# STM32F103RCT6_2_0.net
KiCad netlist of a schematic drawn in EasyEDA Pro
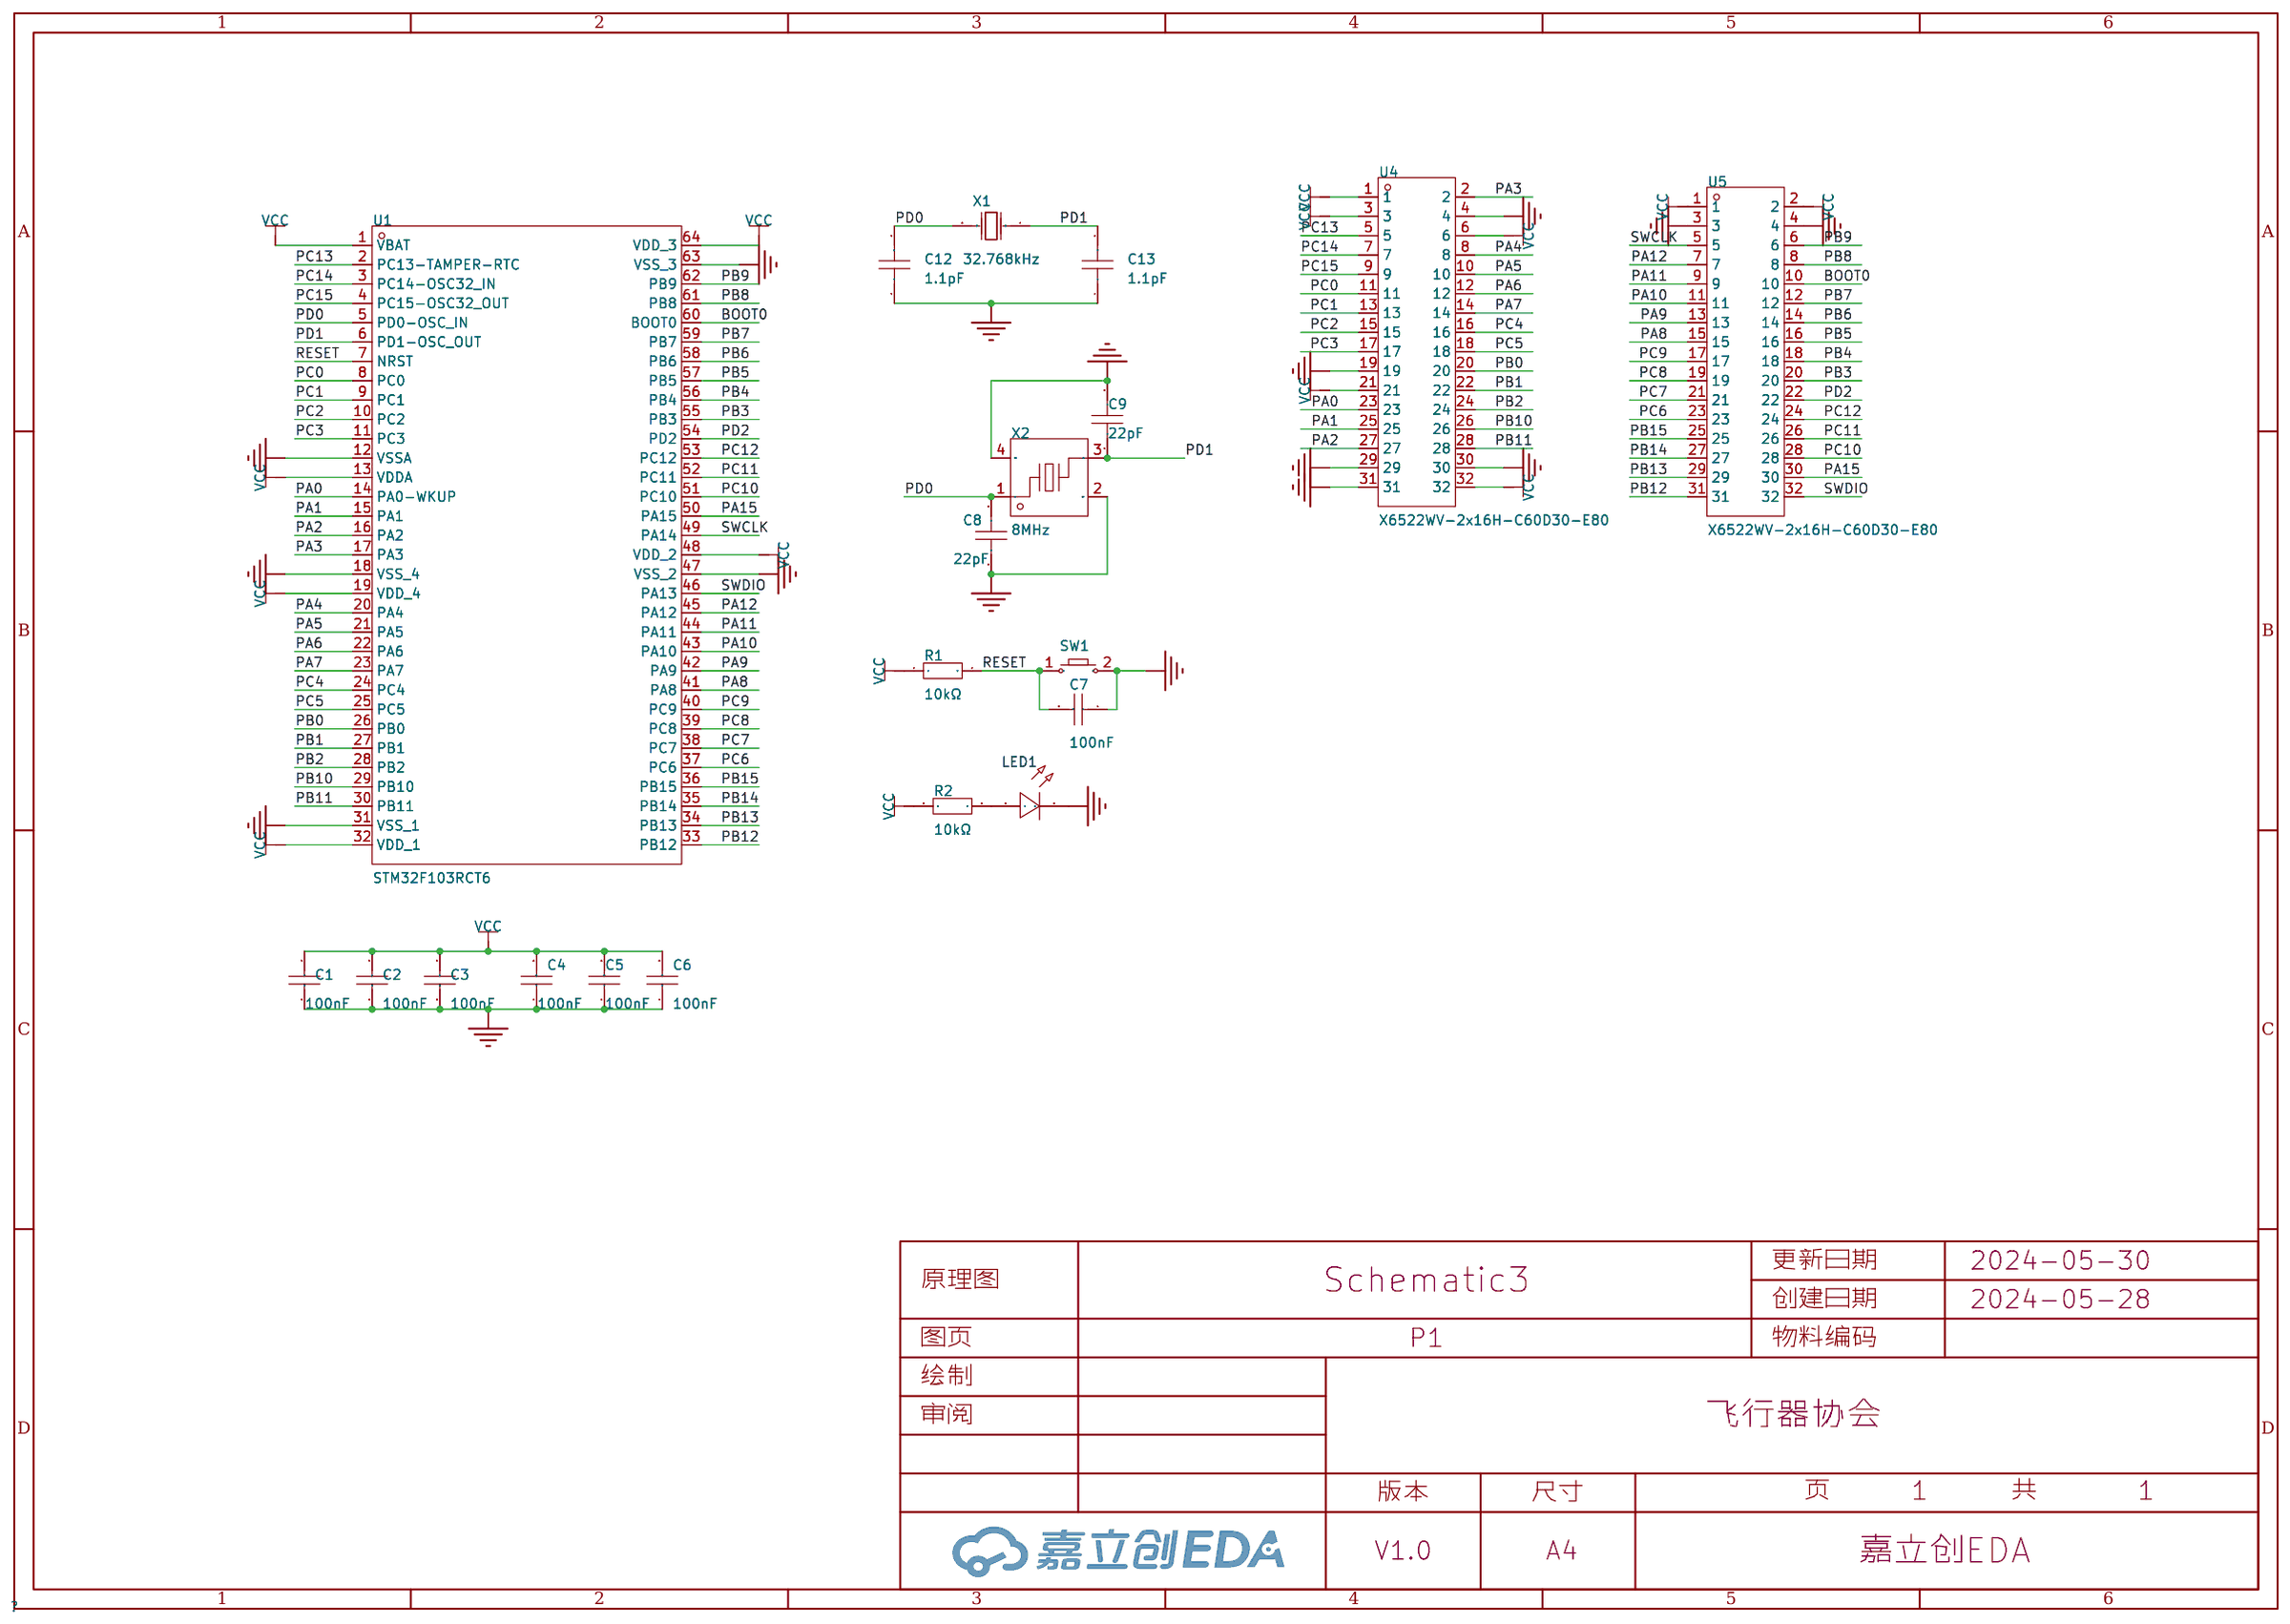
[diagram p0: schematic sheet]

(export (version "E")
  (design (tool "Eeschema 10.0.6"))
  (components
    (comp (ref "C1")
      (value "100nF")
      (footprint "easyedapro:C0805")
      (description "容值:100nF;精度:±10%;额定电压:50V;材质(温度系数):X7R;")
      (fields
        (field (name "Manufacturer Part") "CC0805KRX7R9BB104")
        (field (name "Manufacturer") "YAGEO(国巨)")
      )
      (libsource (lib "easyedapro") (part "CC0805KRX7R9BB104"))
    )
    (comp (ref "C2")
      (value "100nF")
      (footprint "easyedapro:C0805")
      (description "容值:100nF;精度:±10%;额定电压:50V;材质(温度系数):X7R;")
      (fields
        (field (name "Manufacturer Part") "CC0805KRX7R9BB104")
        (field (name "Manufacturer") "YAGEO(国巨)")
      )
      (libsource (lib "easyedapro") (part "CC0805KRX7R9BB104"))
    )
    (comp (ref "C3")
      (value "100nF")
      (footprint "easyedapro:C0805")
      (description "容值:100nF;精度:±10%;额定电压:50V;材质(温度系数):X7R;")
      (fields
        (field (name "Manufacturer Part") "CC0805KRX7R9BB104")
        (field (name "Manufacturer") "YAGEO(国巨)")
      )
      (libsource (lib "easyedapro") (part "CC0805KRX7R9BB104"))
    )
    (comp (ref "C4")
      (value "100nF")
      (footprint "easyedapro:C0805")
      (description "容值:100nF;精度:±10%;额定电压:50V;材质(温度系数):X7R;")
      (fields
        (field (name "Manufacturer Part") "CC0805KRX7R9BB104")
        (field (name "Manufacturer") "YAGEO(国巨)")
      )
      (libsource (lib "easyedapro") (part "CC0805KRX7R9BB104"))
    )
    (comp (ref "C5")
      (value "100nF")
      (footprint "easyedapro:C0805")
      (description "容值:100nF;精度:±10%;额定电压:50V;材质(温度系数):X7R;")
      (fields
        (field (name "Manufacturer Part") "CC0805KRX7R9BB104")
        (field (name "Manufacturer") "YAGEO(国巨)")
      )
      (libsource (lib "easyedapro") (part "CC0805KRX7R9BB104"))
    )
    (comp (ref "C6")
      (value "100nF")
      (footprint "easyedapro:C0805")
      (description "容值:100nF;精度:±10%;额定电压:50V;材质(温度系数):X7R;")
      (fields
        (field (name "Manufacturer Part") "CC0805KRX7R9BB104")
        (field (name "Manufacturer") "YAGEO(国巨)")
      )
      (libsource (lib "easyedapro") (part "CC0805KRX7R9BB104"))
    )
    (comp (ref "C7")
      (value "100nF")
      (footprint "easyedapro:C0805")
      (description "容值:100nF;精度:±10%;额定电压:50V;材质(温度系数):X7R;")
      (fields
        (field (name "Manufacturer Part") "CC0805KRX7R9BB104")
        (field (name "Manufacturer") "YAGEO(国巨)")
      )
      (libsource (lib "easyedapro") (part "CC0805KRX7R9BB104"))
    )
    (comp (ref "C8")
      (value "22pF")
      (footprint "easyedapro:C0805")
      (description "容值:22pF;精度:±5%;额定电压:50V;材质(温度系数):C0G;")
      (fields (field (name "Manufacturer Part") "0805CG220J500NT") (field (name "Manufacturer") "FH(风华)"))
      (libsource (lib "easyedapro") (part "0805CG220J500NT_C24658"))
    )
    (comp (ref "C9")
      (value "22pF")
      (footprint "easyedapro:C0805")
      (description "容值:22pF;精度:±5%;额定电压:50V;材质(温度系数):C0G;")
      (fields (field (name "Manufacturer Part") "0805CG220J500NT") (field (name "Manufacturer") "FH(风华)"))
      (libsource (lib "easyedapro") (part "0805CG220J500NT_C24658"))
    )
    (comp (ref "C12")
      (value "1.1pF")
      (footprint "easyedapro:C0805")
      (description "容值:1.1pF;额定电压:250V;材质(温度系数):C0G;")
      (fields (field (name "Manufacturer Part") "VJ0805D1R1CXPAC") (field (name "Manufacturer") "VISHAY(威世)"))
      (libsource (lib "easyedapro") (part "VJ0805D1R1CXPAC"))
    )
    (comp (ref "C13")
      (value "1.1pF")
      (footprint "easyedapro:C0805")
      (description "容值:1.1pF;额定电压:250V;材质(温度系数):C0G;")
      (fields (field (name "Manufacturer Part") "VJ0805D1R1CXPAC") (field (name "Manufacturer") "VISHAY(威世)"))
      (libsource (lib "easyedapro") (part "VJ0805D1R1CXPAC"))
    )
    (comp (ref "LED1")
      (value "~")
      (footprint "easyedapro:LED_0805")
      (libsource (lib "easyedapro") (part "LED_G"))
    )
    (comp (ref "R1")
      (value "10kΩ")
      (footprint "easyedapro:R0805")
      (description "电阻类型:厚膜电阻;阻值:10kΩ;精度:±1%;功率:125mW;最大工作电压:150V;温度系数:±100ppm/°C;")
      (fields
        (field (name "Manufacturer Part") "0805W8F1002T5E")
        (field (name "Manufacturer") "UNI-ROYAL(厚声)")
      )
      (libsource (lib "easyedapro") (part "0805W8F1002T5E"))
    )
    (comp (ref "R2")
      (value "10kΩ")
      (footprint "easyedapro:R0805")
      (description "电阻类型:厚膜电阻;阻值:10kΩ;精度:±1%;功率:125mW;最大工作电压:150V;温度系数:±100ppm/°C;")
      (fields
        (field (name "Manufacturer Part") "0805W8F1002T5E")
        (field (name "Manufacturer") "UNI-ROYAL(厚声)")
      )
      (libsource (lib "easyedapro") (part "0805W8F1002T5E"))
    )
    (comp (ref "SW1")
      (value "~")
      (footprint "easyedapro:Key_SMD_3.6x6.1x2.5")
      (libsource (lib "easyedapro") (part "轻触按键x2"))
    )
    (comp (ref "U1")
      (value "STM32F103RCT6")
      (footprint "easyedapro:LQFP-64_L10.0-W10.0-P0.50-LS12.0-BL")
      (fields (field (name "Manufacturer") "ST(意法半导体)"))
      (libsource (lib "easyedapro") (part "STM32F103RCT6"))
    )
    (comp (ref "U4")
      (value "X6522WV-2x16H-C60D30-E80")
      (footprint "easyedapro:HDR-TH_32P-P2.54-V-M-R2-C16-S2.54-3")
      (fields (field (name "Manufacturer") "XKB Connection(中国星坤)"))
      (libsource (lib "easyedapro") (part "X6522WV-2X16H-C60D30-E80"))
    )
    (comp (ref "U5")
      (value "X6522WV-2x16H-C60D30-E80")
      (footprint "easyedapro:HDR-TH_32P-P2.54-V-M-R2-C16-S2.54-3")
      (fields (field (name "Manufacturer") "XKB Connection(中国星坤)"))
      (libsource (lib "easyedapro") (part "X6522WV-2X16H-C60D30-E80"))
    )
    (comp (ref "X1")
      (value "32.768kHz")
      (footprint "easyedapro:OSC-TH_BD2.0-P0.70-D0.3")
      (description "晶振类型:-;频率:-;外接负载电容:-;")
      (fields (field (name "Manufacturer Part") "DT-26 32.768KHz") (field (name "Manufacturer") "KDS(大真空)"))
      (libsource (lib "easyedapro") (part "DT-26 32.768KHz"))
    )
    (comp (ref "X2")
      (value "8MHz")
      (footprint "easyedapro:CRYSTAL-SMD_4P-L3.2-W2.5-BL")
      (description "晶振类型:-;频率:8MHz;常温频差:±10ppm;外接负载电容:20pF;频率稳定度(全温):±30ppm;")
      (fields
        (field (name "Manufacturer Part") "3225 8M 20PF 10PPM")
        (field (name "Manufacturer") "SST(索斯特)")
      )
      (libsource (lib "easyedapro") (part "3225 8M 20PF 10PPM"))
    )
  )
  (nets
    (net (code "1") (name "/BOOT0") (class "Default")
      (node (ref "U1") (pin "60") (pinfunction "BOOT0_60") (pintype "unspecified"))
      (node (ref "U5") (pin "10") (pinfunction "10_10") (pintype "unspecified"))
    )
    (net (code "2") (name "/PA0") (class "Default")
      (node (ref "U1") (pin "14") (pinfunction "PA0-WKUP_14") (pintype "unspecified"))
      (node (ref "U4") (pin "23") (pinfunction "23_23") (pintype "unspecified"))
    )
    (net (code "3") (name "/PA1") (class "Default")
      (node (ref "U1") (pin "15") (pinfunction "PA1_15") (pintype "unspecified"))
      (node (ref "U4") (pin "25") (pinfunction "25_25") (pintype "unspecified"))
    )
    (net (code "4") (name "/PA2") (class "Default")
      (node (ref "U1") (pin "16") (pinfunction "PA2_16") (pintype "unspecified"))
      (node (ref "U4") (pin "27") (pinfunction "27_27") (pintype "unspecified"))
    )
    (net (code "5") (name "/PA3") (class "Default")
      (node (ref "U1") (pin "17") (pinfunction "PA3_17") (pintype "unspecified"))
      (node (ref "U4") (pin "2") (pinfunction "2_2") (pintype "unspecified"))
    )
    (net (code "6") (name "/PA4") (class "Default")
      (node (ref "U1") (pin "20") (pinfunction "PA4_20") (pintype "unspecified"))
      (node (ref "U4") (pin "8") (pinfunction "8_8") (pintype "unspecified"))
    )
    (net (code "7") (name "/PA5") (class "Default")
      (node (ref "U1") (pin "21") (pinfunction "PA5_21") (pintype "unspecified"))
      (node (ref "U4") (pin "10") (pinfunction "10_10") (pintype "unspecified"))
    )
    (net (code "8") (name "/PA6") (class "Default")
      (node (ref "U1") (pin "22") (pinfunction "PA6_22") (pintype "unspecified"))
      (node (ref "U4") (pin "12") (pinfunction "12_12") (pintype "unspecified"))
    )
    (net (code "9") (name "/PA7") (class "Default")
      (node (ref "U1") (pin "23") (pinfunction "PA7_23") (pintype "unspecified"))
      (node (ref "U4") (pin "14") (pinfunction "14_14") (pintype "unspecified"))
    )
    (net (code "10") (name "/PA8") (class "Default")
      (node (ref "U1") (pin "41") (pinfunction "PA8_41") (pintype "unspecified"))
      (node (ref "U5") (pin "15") (pinfunction "15_15") (pintype "unspecified"))
    )
    (net (code "11") (name "/PA9") (class "Default")
      (node (ref "U1") (pin "42") (pinfunction "PA9_42") (pintype "unspecified"))
      (node (ref "U5") (pin "13") (pinfunction "13_13") (pintype "unspecified"))
    )
    (net (code "12") (name "/PA10") (class "Default")
      (node (ref "U1") (pin "43") (pinfunction "PA10_43") (pintype "unspecified"))
      (node (ref "U5") (pin "11") (pinfunction "11_11") (pintype "unspecified"))
    )
    (net (code "13") (name "/PA11") (class "Default")
      (node (ref "U1") (pin "44") (pinfunction "PA11_44") (pintype "unspecified"))
      (node (ref "U5") (pin "9") (pinfunction "9_9") (pintype "unspecified"))
    )
    (net (code "14") (name "/PA12") (class "Default")
      (node (ref "U1") (pin "45") (pinfunction "PA12_45") (pintype "unspecified"))
      (node (ref "U5") (pin "7") (pinfunction "7_7") (pintype "unspecified"))
    )
    (net (code "15") (name "/PA15") (class "Default")
      (node (ref "U1") (pin "50") (pinfunction "PA15_50") (pintype "unspecified"))
      (node (ref "U5") (pin "30") (pinfunction "30_30") (pintype "unspecified"))
    )
    (net (code "16") (name "/PB0") (class "Default")
      (node (ref "U1") (pin "26") (pinfunction "PB0_26") (pintype "unspecified"))
      (node (ref "U4") (pin "20") (pinfunction "20_20") (pintype "unspecified"))
    )
    (net (code "17") (name "/PB1") (class "Default")
      (node (ref "U1") (pin "27") (pinfunction "PB1_27") (pintype "unspecified"))
      (node (ref "U4") (pin "22") (pinfunction "22_22") (pintype "unspecified"))
    )
    (net (code "18") (name "/PB2") (class "Default")
      (node (ref "U1") (pin "28") (pinfunction "PB2_28") (pintype "unspecified"))
      (node (ref "U4") (pin "24") (pinfunction "24_24") (pintype "unspecified"))
    )
    (net (code "19") (name "/PB3") (class "Default")
      (node (ref "U1") (pin "55") (pinfunction "PB3_55") (pintype "unspecified"))
      (node (ref "U5") (pin "20") (pinfunction "20_20") (pintype "unspecified"))
    )
    (net (code "20") (name "/PB4") (class "Default")
      (node (ref "U1") (pin "56") (pinfunction "PB4_56") (pintype "unspecified"))
      (node (ref "U5") (pin "18") (pinfunction "18_18") (pintype "unspecified"))
    )
    (net (code "21") (name "/PB5") (class "Default")
      (node (ref "U1") (pin "57") (pinfunction "PB5_57") (pintype "unspecified"))
      (node (ref "U5") (pin "16") (pinfunction "16_16") (pintype "unspecified"))
    )
    (net (code "22") (name "/PB6") (class "Default")
      (node (ref "U1") (pin "58") (pinfunction "PB6_58") (pintype "unspecified"))
      (node (ref "U5") (pin "14") (pinfunction "14_14") (pintype "unspecified"))
    )
    (net (code "23") (name "/PB7") (class "Default")
      (node (ref "U1") (pin "59") (pinfunction "PB7_59") (pintype "unspecified"))
      (node (ref "U5") (pin "12") (pinfunction "12_12") (pintype "unspecified"))
    )
    (net (code "24") (name "/PB8") (class "Default")
      (node (ref "U1") (pin "61") (pinfunction "PB8_61") (pintype "unspecified"))
      (node (ref "U5") (pin "8") (pinfunction "8_8") (pintype "unspecified"))
    )
    (net (code "25") (name "/PB9") (class "Default")
      (node (ref "U1") (pin "62") (pinfunction "PB9_62") (pintype "unspecified"))
      (node (ref "U5") (pin "6") (pinfunction "6_6") (pintype "unspecified"))
    )
    (net (code "26") (name "/PB10") (class "Default")
      (node (ref "U1") (pin "29") (pinfunction "PB10_29") (pintype "unspecified"))
      (node (ref "U4") (pin "26") (pinfunction "26_26") (pintype "unspecified"))
    )
    (net (code "27") (name "/PB11") (class "Default")
      (node (ref "U1") (pin "30") (pinfunction "PB11_30") (pintype "unspecified"))
      (node (ref "U4") (pin "28") (pinfunction "28_28") (pintype "unspecified"))
    )
    (net (code "28") (name "/PB12") (class "Default")
      (node (ref "U1") (pin "33") (pinfunction "PB12_33") (pintype "unspecified"))
      (node (ref "U5") (pin "31") (pinfunction "31_31") (pintype "unspecified"))
    )
    (net (code "29") (name "/PB13") (class "Default")
      (node (ref "U1") (pin "34") (pinfunction "PB13_34") (pintype "unspecified"))
      (node (ref "U5") (pin "29") (pinfunction "29_29") (pintype "unspecified"))
    )
    (net (code "30") (name "/PB14") (class "Default")
      (node (ref "U1") (pin "35") (pinfunction "PB14_35") (pintype "unspecified"))
      (node (ref "U5") (pin "27") (pinfunction "27_27") (pintype "unspecified"))
    )
    (net (code "31") (name "/PB15") (class "Default")
      (node (ref "U1") (pin "36") (pinfunction "PB15_36") (pintype "unspecified"))
      (node (ref "U5") (pin "25") (pinfunction "25_25") (pintype "unspecified"))
    )
    (net (code "32") (name "/PC0") (class "Default")
      (node (ref "U1") (pin "8") (pinfunction "PC0_8") (pintype "unspecified"))
      (node (ref "U4") (pin "11") (pinfunction "11_11") (pintype "unspecified"))
    )
    (net (code "33") (name "/PC1") (class "Default")
      (node (ref "U1") (pin "9") (pinfunction "PC1_9") (pintype "unspecified"))
      (node (ref "U4") (pin "13") (pinfunction "13_13") (pintype "unspecified"))
    )
    (net (code "34") (name "/PC2") (class "Default")
      (node (ref "U1") (pin "10") (pinfunction "PC2_10") (pintype "unspecified"))
      (node (ref "U4") (pin "15") (pinfunction "15_15") (pintype "unspecified"))
    )
    (net (code "35") (name "/PC3") (class "Default")
      (node (ref "U1") (pin "11") (pinfunction "PC3_11") (pintype "unspecified"))
      (node (ref "U4") (pin "17") (pinfunction "17_17") (pintype "unspecified"))
    )
    (net (code "36") (name "/PC4") (class "Default")
      (node (ref "U1") (pin "24") (pinfunction "PC4_24") (pintype "unspecified"))
      (node (ref "U4") (pin "16") (pinfunction "16_16") (pintype "unspecified"))
    )
    (net (code "37") (name "/PC5") (class "Default")
      (node (ref "U1") (pin "25") (pinfunction "PC5_25") (pintype "unspecified"))
      (node (ref "U4") (pin "18") (pinfunction "18_18") (pintype "unspecified"))
    )
    (net (code "38") (name "/PC6") (class "Default")
      (node (ref "U1") (pin "37") (pinfunction "PC6_37") (pintype "unspecified"))
      (node (ref "U5") (pin "23") (pinfunction "23_23") (pintype "unspecified"))
    )
    (net (code "39") (name "/PC7") (class "Default")
      (node (ref "U1") (pin "38") (pinfunction "PC7_38") (pintype "unspecified"))
      (node (ref "U5") (pin "21") (pinfunction "21_21") (pintype "unspecified"))
    )
    (net (code "40") (name "/PC8") (class "Default")
      (node (ref "U1") (pin "39") (pinfunction "PC8_39") (pintype "unspecified"))
      (node (ref "U5") (pin "19") (pinfunction "19_19") (pintype "unspecified"))
    )
    (net (code "41") (name "/PC9") (class "Default")
      (node (ref "U1") (pin "40") (pinfunction "PC9_40") (pintype "unspecified"))
      (node (ref "U5") (pin "17") (pinfunction "17_17") (pintype "unspecified"))
    )
    (net (code "42") (name "/PC10") (class "Default")
      (node (ref "U1") (pin "51") (pinfunction "PC10_51") (pintype "unspecified"))
      (node (ref "U5") (pin "28") (pinfunction "28_28") (pintype "unspecified"))
    )
    (net (code "43") (name "/PC11") (class "Default")
      (node (ref "U1") (pin "52") (pinfunction "PC11_52") (pintype "unspecified"))
      (node (ref "U5") (pin "26") (pinfunction "26_26") (pintype "unspecified"))
    )
    (net (code "44") (name "/PC12") (class "Default")
      (node (ref "U1") (pin "53") (pinfunction "PC12_53") (pintype "unspecified"))
      (node (ref "U5") (pin "24") (pinfunction "24_24") (pintype "unspecified"))
    )
    (net (code "45") (name "/PC13") (class "Default")
      (node (ref "U1") (pin "2") (pinfunction "PC13-TAMPER-RTC_2") (pintype "unspecified"))
      (node (ref "U4") (pin "5") (pinfunction "5_5") (pintype "unspecified"))
    )
    (net (code "46") (name "/PC14") (class "Default")
      (node (ref "U1") (pin "3") (pinfunction "PC14-OSC32_IN_3") (pintype "unspecified"))
      (node (ref "U4") (pin "7") (pinfunction "7_7") (pintype "unspecified"))
    )
    (net (code "47") (name "/PC15") (class "Default")
      (node (ref "U1") (pin "4") (pinfunction "PC15-OSC32_OUT_4") (pintype "unspecified"))
      (node (ref "U4") (pin "9") (pinfunction "9_9") (pintype "unspecified"))
    )
    (net (code "48") (name "/PD0") (class "Default")
      (node (ref "C12") (pin "2") (pinfunction "2_2") (pintype "unspecified"))
      (node (ref "C8") (pin "2") (pinfunction "2_2") (pintype "unspecified"))
      (node (ref "U1") (pin "5") (pinfunction "PD0-OSC_IN_5") (pintype "unspecified"))
      (node (ref "X1") (pin "2") (pinfunction "OSC2_2") (pintype "input"))
      (node (ref "X2") (pin "1") (pinfunction "1_1") (pintype "input"))
    )
    (net (code "49") (name "/PD1") (class "Default")
      (node (ref "C13") (pin "2") (pinfunction "2_2") (pintype "unspecified"))
      (node (ref "C9") (pin "1") (pinfunction "1_1") (pintype "unspecified"))
      (node (ref "U1") (pin "6") (pinfunction "PD1-OSC_OUT_6") (pintype "unspecified"))
      (node (ref "X1") (pin "1") (pinfunction "OSC1_1") (pintype "input"))
      (node (ref "X2") (pin "3") (pinfunction "3_3") (pintype "input"))
    )
    (net (code "50") (name "/PD2") (class "Default")
      (node (ref "U1") (pin "54") (pinfunction "PD2_54") (pintype "unspecified"))
      (node (ref "U5") (pin "22") (pinfunction "22_22") (pintype "unspecified"))
    )
    (net (code "51") (name "/RESET") (class "Default")
      (node (ref "C7") (pin "2") (pinfunction "2_2") (pintype "input"))
      (node (ref "R1") (pin "2") (pinfunction "2_2") (pintype "input"))
      (node (ref "SW1") (pin "1") (pinfunction "1_1") (pintype "input"))
      (node (ref "U1") (pin "7") (pinfunction "NRST_7") (pintype "unspecified"))
    )
    (net (code "52") (name "/SWCLK") (class "Default")
      (node (ref "U1") (pin "49") (pinfunction "PA14_49") (pintype "unspecified"))
      (node (ref "U5") (pin "5") (pinfunction "5_5") (pintype "unspecified"))
    )
    (net (code "53") (name "/SWDIO") (class "Default")
      (node (ref "U1") (pin "46") (pinfunction "PA13_46") (pintype "unspecified"))
      (node (ref "U5") (pin "32") (pinfunction "32_32") (pintype "unspecified"))
    )
    (net (code "54") (name "GND") (class "Default")
      (node (ref "C1") (pin "1") (pinfunction "1_1") (pintype "input"))
      (node (ref "C12") (pin "1") (pinfunction "1_1") (pintype "unspecified"))
      (node (ref "C13") (pin "1") (pinfunction "1_1") (pintype "unspecified"))
      (node (ref "C2") (pin "1") (pinfunction "1_1") (pintype "input"))
      (node (ref "C3") (pin "1") (pinfunction "1_1") (pintype "input"))
      (node (ref "C4") (pin "1") (pinfunction "1_1") (pintype "input"))
      (node (ref "C5") (pin "1") (pinfunction "1_1") (pintype "input"))
      (node (ref "C6") (pin "1") (pinfunction "1_1") (pintype "input"))
      (node (ref "C7") (pin "1") (pinfunction "1_1") (pintype "input"))
      (node (ref "C8") (pin "1") (pinfunction "1_1") (pintype "unspecified"))
      (node (ref "C9") (pin "2") (pinfunction "2_2") (pintype "unspecified"))
      (node (ref "LED1") (pin "1") (pinfunction "C_1") (pintype "input"))
      (node (ref "SW1") (pin "2") (pinfunction "2_2") (pintype "input"))
      (node (ref "U1") (pin "12") (pinfunction "VSSA_12") (pintype "unspecified"))
      (node (ref "U1") (pin "18") (pinfunction "VSS_4_18") (pintype "unspecified"))
      (node (ref "U1") (pin "31") (pinfunction "VSS_1_31") (pintype "unspecified"))
      (node (ref "U1") (pin "47") (pinfunction "VSS_2_47") (pintype "unspecified"))
      (node (ref "U1") (pin "63") (pinfunction "VSS_3_63") (pintype "unspecified"))
      (node (ref "U4") (pin "19") (pinfunction "19_19") (pintype "unspecified"))
      (node (ref "U4") (pin "29") (pinfunction "29_29") (pintype "unspecified"))
      (node (ref "U4") (pin "30") (pinfunction "30_30") (pintype "unspecified"))
      (node (ref "U4") (pin "31") (pinfunction "31_31") (pintype "unspecified"))
      (node (ref "U4") (pin "4") (pinfunction "4_4") (pintype "unspecified"))
      (node (ref "U5") (pin "3") (pinfunction "3_3") (pintype "unspecified"))
      (node (ref "U5") (pin "4") (pinfunction "4_4") (pintype "unspecified"))
      (node (ref "X2") (pin "2") (pinfunction "GND_2") (pintype "input"))
      (node (ref "X2") (pin "4") (pinfunction "GND_4") (pintype "input"))
    )
    (net (code "55") (name "Net-(LED1-A)") (class "Default")
      (node (ref "LED1") (pin "2") (pinfunction "A_2") (pintype "input"))
      (node (ref "R2") (pin "2") (pinfunction "2_2") (pintype "input"))
    )
    (net (code "56") (name "VCC") (class "Default")
      (node (ref "C1") (pin "2") (pinfunction "2_2") (pintype "input"))
      (node (ref "C2") (pin "2") (pinfunction "2_2") (pintype "input"))
      (node (ref "C3") (pin "2") (pinfunction "2_2") (pintype "input"))
      (node (ref "C4") (pin "2") (pinfunction "2_2") (pintype "input"))
      (node (ref "C5") (pin "2") (pinfunction "2_2") (pintype "input"))
      (node (ref "C6") (pin "2") (pinfunction "2_2") (pintype "input"))
      (node (ref "R1") (pin "1") (pinfunction "1_1") (pintype "input"))
      (node (ref "R2") (pin "1") (pinfunction "1_1") (pintype "input"))
      (node (ref "U1") (pin "1") (pinfunction "VBAT_1") (pintype "unspecified"))
      (node (ref "U1") (pin "13") (pinfunction "VDDA_13") (pintype "unspecified"))
      (node (ref "U1") (pin "19") (pinfunction "VDD_4_19") (pintype "unspecified"))
      (node (ref "U1") (pin "32") (pinfunction "VDD_1_32") (pintype "unspecified"))
      (node (ref "U1") (pin "48") (pinfunction "VDD_2_48") (pintype "unspecified"))
      (node (ref "U1") (pin "64") (pinfunction "VDD_3_64") (pintype "unspecified"))
      (node (ref "U4") (pin "1") (pinfunction "1_1") (pintype "unspecified"))
      (node (ref "U4") (pin "21") (pinfunction "21_21") (pintype "unspecified"))
      (node (ref "U4") (pin "3") (pinfunction "3_3") (pintype "unspecified"))
      (node (ref "U4") (pin "32") (pinfunction "32_32") (pintype "unspecified"))
      (node (ref "U4") (pin "6") (pinfunction "6_6") (pintype "unspecified"))
      (node (ref "U5") (pin "1") (pinfunction "1_1") (pintype "unspecified"))
      (node (ref "U5") (pin "2") (pinfunction "2_2") (pintype "unspecified"))
    )
  )
)
